# Sensors.net
KiCad netlist of a schematic drawn in Altium Designer
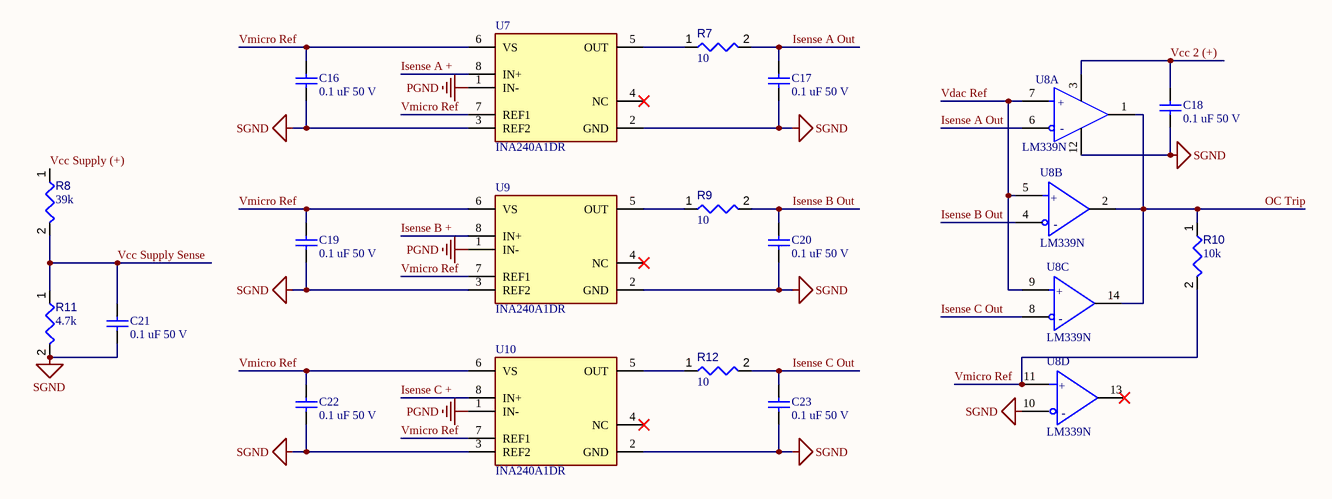
[diagram p0: Sensors.SchDoc]

(export (version "E")
  (design (tool "Eeschema 10.0.6"))
  (components
    (comp (ref "C16")
      (value "0.1 uF 50 V")
      (footprint "CAPR51-254-508X318X736")
      (libsource (lib "Altium Content Vault") (part "CAP-NP-2"))
    )
    (comp (ref "C17")
      (value "0.1 uF 50 V")
      (footprint "CAPR51-254-508X318X736")
      (libsource (lib "Altium Content Vault") (part "CAP-NP-2"))
    )
    (comp (ref "C18")
      (value "0.1 uF 50 V")
      (footprint "CAPR51-254-508X318X736")
      (libsource (lib "Altium Content Vault") (part "CAP-NP-2"))
    )
    (comp (ref "C19")
      (value "0.1 uF 50 V")
      (footprint "CAPR51-254-508X318X736")
      (libsource (lib "Altium Content Vault") (part "CAP-NP-2"))
    )
    (comp (ref "C20")
      (value "0.1 uF 50 V")
      (footprint "CAPR51-254-508X318X736")
      (libsource (lib "Altium Content Vault") (part "CAP-NP-2"))
    )
    (comp (ref "C21")
      (value "0.1 uF 50 V")
      (footprint "CAPR51-254-508X318X736")
      (libsource (lib "Altium Content Vault") (part "CAP-NP-2"))
    )
    (comp (ref "C22")
      (value "0.1 uF 50 V")
      (footprint "CAPR51-254-508X318X736")
      (libsource (lib "Altium Content Vault") (part "CAP-NP-2"))
    )
    (comp (ref "C23")
      (value "0.1 uF 50 V")
      (footprint "CAPR51-254-508X318X736")
      (libsource (lib "Altium Content Vault") (part "CAP-NP-2"))
    )
    (comp (ref "R7")
      (value "10")
      (footprint "RESA60-630X240")
      (description "10 Ohms ±1% 0.25W, 1/4W Through Hole Resistor Axial Metal Film")
      (fields (field (name "TOLERANCE") "1%") (field (name "POWER") "250mW"))
      (libsource (lib "Pessoal") (part "RES-2"))
    )
    (comp (ref "R8")
      (value "39k")
      (footprint "RESA60-630X240")
      (description "39 kOhms ±1% 0.25W, 1/4W Through Hole Resistor Axial Metal Film")
      (fields (field (name "TOLERANCE") "1%") (field (name "POWER") "250mW"))
      (libsource (lib "Pessoal") (part "RES-2"))
    )
    (comp (ref "R9")
      (value "10")
      (footprint "RESA60-630X240")
      (description "10 Ohms ±1% 0.25W, 1/4W Through Hole Resistor Axial Metal Film")
      (fields (field (name "TOLERANCE") "1%") (field (name "POWER") "250mW"))
      (libsource (lib "Pessoal") (part "RES-2"))
    )
    (comp (ref "R10")
      (value "10k")
      (footprint "RESA60-630X240")
      (description "10 kOhms ±1% 0.25W, 1/4W Through Hole Resistor Axial Metal Film")
      (fields (field (name "TOLERANCE") "1%") (field (name "POWER") "250mW"))
      (libsource (lib "Pessoal") (part "RES-2"))
    )
    (comp (ref "R11")
      (value "4.7k")
      (footprint "RESA60-630X240")
      (description "4.7 kOhms ±1% 0.25W, 1/4W Through Hole Resistor Axial Metal Film")
      (fields (field (name "TOLERANCE") "1%") (field (name "POWER") "250mW"))
      (libsource (lib "Pessoal") (part "RES-2"))
    )
    (comp (ref "R12")
      (value "10")
      (footprint "RESA60-630X240")
      (description "10 Ohms ±1% 0.25W, 1/4W Through Hole Resistor Axial Metal Film")
      (fields (field (name "TOLERANCE") "1%") (field (name "POWER") "250mW"))
      (libsource (lib "Pessoal") (part "RES-2"))
    )
    (comp (ref "U7")
      (value "INA240A1DR")
      (footprint "FP-D0008A-IPC_A")
      (description "IC CURR SENSE 1 CIRCUIT 8SOIC")
      (libsource (lib "Altium Content Vault") (part "a9db4a8a3d73c22b64f8e8a0c239388"))
    )
    (comp (ref "U8")
      (value "LM339N")
      (footprint "FP-N0014A-MFG")
      (description "IC QUAD DIFF COMPARATOR 14-DIP")
      (libsource (lib "Altium Content Vault") (part "8b3fbf4f291bf98688575f76bf8ab1e"))
    )
    (comp (ref "U9")
      (value "INA240A1DR")
      (footprint "FP-D0008A-IPC_A")
      (description "IC CURR SENSE 1 CIRCUIT 8SOIC")
      (libsource (lib "Altium Content Vault") (part "a9db4a8a3d73c22b64f8e8a0c239388"))
    )
    (comp (ref "U10")
      (value "INA240A1DR")
      (footprint "FP-D0008A-IPC_A")
      (description "IC CURR SENSE 1 CIRCUIT 8SOIC")
      (libsource (lib "Altium Content Vault") (part "a9db4a8a3d73c22b64f8e8a0c239388"))
    )
  )
  (nets
    (net (code "1") (name "/Isense A +") (class "Default")
      (node (ref "U7") (pin "8") (pinfunction "IN+_8") (pintype "tri_state"))
    )
    (net (code "2") (name "/Isense A Out") (class "Default")
      (node (ref "C17") (pin "2") (pinfunction "2_2") (pintype "passive"))
      (node (ref "R7") (pin "2") (pinfunction "2_2") (pintype "passive"))
      (node (ref "U8") (pin "6") (pinfunction "1IN-_6") (pintype "tri_state"))
    )
    (net (code "3") (name "/Isense B +") (class "Default")
      (node (ref "U9") (pin "8") (pinfunction "IN+_8") (pintype "tri_state"))
    )
    (net (code "4") (name "/Isense B Out") (class "Default")
      (node (ref "C20") (pin "2") (pinfunction "2_2") (pintype "passive"))
      (node (ref "R9") (pin "2") (pinfunction "2_2") (pintype "passive"))
      (node (ref "U8") (pin "4") (pinfunction "2IN-_4") (pintype "tri_state"))
    )
    (net (code "5") (name "/Isense C +") (class "Default")
      (node (ref "U10") (pin "8") (pinfunction "IN+_8") (pintype "tri_state"))
    )
    (net (code "6") (name "/Isense C Out") (class "Default")
      (node (ref "C23") (pin "2") (pinfunction "2_2") (pintype "passive"))
      (node (ref "R12") (pin "2") (pinfunction "2_2") (pintype "passive"))
      (node (ref "U8") (pin "8") (pinfunction "3IN-_8") (pintype "tri_state"))
    )
    (net (code "7") (name "/OC Trip") (class "Default")
      (node (ref "R10") (pin "1") (pinfunction "1_1") (pintype "passive"))
      (node (ref "U8") (pin "1") (pinfunction "1OUT_1") (pintype "passive"))
      (node (ref "U8") (pin "14") (pinfunction "OUT3_14") (pintype "passive"))
      (node (ref "U8") (pin "2") (pinfunction "2OUT_2") (pintype "passive"))
    )
    (net (code "8") (name "/Vcc 2 (+)") (class "Default")
      (node (ref "C18") (pin "2") (pinfunction "2_2") (pintype "passive"))
      (node (ref "U8") (pin "3") (pinfunction "VCC_3") (pintype "power_in"))
    )
    (net (code "9") (name "/Vcc Supply (+)") (class "Default")
      (node (ref "R8") (pin "1") (pinfunction "1_1") (pintype "passive"))
    )
    (net (code "10") (name "/Vcc Supply Sense") (class "Default")
      (node (ref "C21") (pin "2") (pinfunction "2_2") (pintype "passive"))
      (node (ref "R11") (pin "1") (pinfunction "1_1") (pintype "passive"))
      (node (ref "R8") (pin "2") (pinfunction "2_2") (pintype "passive"))
    )
    (net (code "11") (name "/Vdac Ref") (class "Default")
      (node (ref "U8") (pin "5") (pinfunction "2IN+_5") (pintype "tri_state"))
      (node (ref "U8") (pin "7") (pinfunction "1IN+_7") (pintype "tri_state"))
      (node (ref "U8") (pin "9") (pinfunction "3IN+_9") (pintype "tri_state"))
    )
    (net (code "12") (name "/Vmicro Ref") (class "Default")
      (node (ref "C16") (pin "2") (pinfunction "2_2") (pintype "passive"))
      (node (ref "C19") (pin "2") (pinfunction "2_2") (pintype "passive"))
      (node (ref "C22") (pin "2") (pinfunction "2_2") (pintype "passive"))
      (node (ref "R10") (pin "2") (pinfunction "2_2") (pintype "passive"))
      (node (ref "U10") (pin "6") (pinfunction "VS_6") (pintype "power_in"))
      (node (ref "U10") (pin "7") (pinfunction "REF1_7") (pintype "passive"))
      (node (ref "U7") (pin "6") (pinfunction "VS_6") (pintype "power_in"))
      (node (ref "U7") (pin "7") (pinfunction "REF1_7") (pintype "passive"))
      (node (ref "U8") (pin "11") (pinfunction "4IN+_11") (pintype "tri_state"))
      (node (ref "U9") (pin "6") (pinfunction "VS_6") (pintype "power_in"))
      (node (ref "U9") (pin "7") (pinfunction "REF1_7") (pintype "passive"))
    )
    (net (code "13") (name "Net-(U7-OUT)") (class "Default")
      (node (ref "R7") (pin "1") (pinfunction "1_1") (pintype "passive"))
      (node (ref "U7") (pin "5") (pinfunction "OUT_5") (pintype "passive"))
    )
    (net (code "14") (name "Net-(U9-OUT)") (class "Default")
      (node (ref "R9") (pin "1") (pinfunction "1_1") (pintype "passive"))
      (node (ref "U9") (pin "5") (pinfunction "OUT_5") (pintype "passive"))
    )
    (net (code "15") (name "Net-(U10-OUT)") (class "Default")
      (node (ref "R12") (pin "1") (pinfunction "1_1") (pintype "passive"))
      (node (ref "U10") (pin "5") (pinfunction "OUT_5") (pintype "passive"))
    )
    (net (code "16") (name "PGND") (class "Default")
      (node (ref "U10") (pin "1") (pinfunction "IN-_1") (pintype "tri_state"))
      (node (ref "U7") (pin "1") (pinfunction "IN-_1") (pintype "tri_state"))
      (node (ref "U9") (pin "1") (pinfunction "IN-_1") (pintype "tri_state"))
    )
    (net (code "17") (name "SGND") (class "Default")
      (node (ref "C16") (pin "1") (pinfunction "1_1") (pintype "passive"))
      (node (ref "C17") (pin "1") (pinfunction "1_1") (pintype "passive"))
      (node (ref "C18") (pin "1") (pinfunction "1_1") (pintype "passive"))
      (node (ref "C19") (pin "1") (pinfunction "1_1") (pintype "passive"))
      (node (ref "C20") (pin "1") (pinfunction "1_1") (pintype "passive"))
      (node (ref "C21") (pin "1") (pinfunction "1_1") (pintype "passive"))
      (node (ref "C22") (pin "1") (pinfunction "1_1") (pintype "passive"))
      (node (ref "C23") (pin "1") (pinfunction "1_1") (pintype "passive"))
      (node (ref "R11") (pin "2") (pinfunction "2_2") (pintype "passive"))
      (node (ref "U10") (pin "2") (pinfunction "GND_2") (pintype "power_in"))
      (node (ref "U10") (pin "3") (pinfunction "REF2_3") (pintype "passive"))
      (node (ref "U7") (pin "2") (pinfunction "GND_2") (pintype "power_in"))
      (node (ref "U7") (pin "3") (pinfunction "REF2_3") (pintype "passive"))
      (node (ref "U8") (pin "10") (pinfunction "4IN-_10") (pintype "tri_state"))
      (node (ref "U8") (pin "12") (pinfunction "GND_12") (pintype "power_in"))
      (node (ref "U9") (pin "2") (pinfunction "GND_2") (pintype "power_in"))
      (node (ref "U9") (pin "3") (pinfunction "REF2_3") (pintype "passive"))
    )
    (net (code "18") (name "unconnected-(U7-NC-Pad4)") (class "Default")
      (node (ref "U7") (pin "4") (pinfunction "NC_4") (pintype "passive+no_connect"))
    )
    (net (code "19") (name "unconnected-(U8D-OUT4-Pad13)") (class "Default")
      (node (ref "U8") (pin "13") (pinfunction "OUT4_13") (pintype "passive+no_connect"))
    )
    (net (code "20") (name "unconnected-(U9-NC-Pad4)") (class "Default")
      (node (ref "U9") (pin "4") (pinfunction "NC_4") (pintype "passive+no_connect"))
    )
    (net (code "21") (name "unconnected-(U10-NC-Pad4)") (class "Default")
      (node (ref "U10") (pin "4") (pinfunction "NC_4") (pintype "passive+no_connect"))
    )
  )
)
